# SGWB_circuit.net
KiCad netlist of a schematic drawn in EAGLE
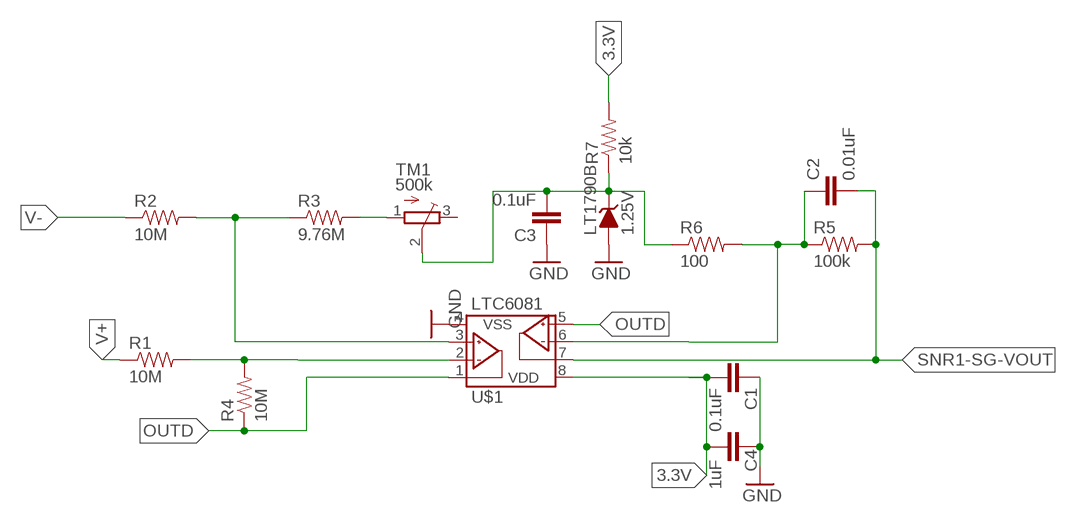
[diagram p0: schematic, sheet 1]

(export (version "E")
  (design (tool "Eeschema 10.0.6"))
  (components
    (comp (ref "C1")
      (value "0.1uF")
      (footprint "eagle-import:0805")
      (libsource (lib "eagle-import") (part "CAP0805"))
    )
    (comp (ref "C2")
      (value "0.01uF")
      (footprint "eagle-import:0805")
      (libsource (lib "eagle-import") (part "CAP0805"))
    )
    (comp (ref "C3")
      (value "0.1uF")
      (footprint "eagle-import:0805")
      (libsource (lib "eagle-import") (part "CAP0805"))
    )
    (comp (ref "C4")
      (value "1uF")
      (footprint "eagle-import:0805")
      (libsource (lib "eagle-import") (part "CAP0805"))
    )
    (comp (ref "LT1790B")
      (value "1.25V")
      (footprint "eagle-import:0805_D")
      (libsource (lib "eagle-import") (part "DIODE_ZENER0805"))
    )
    (comp (ref "R1")
      (value "10M")
      (footprint "eagle-import:0805")
      (libsource (lib "eagle-import") (part "RESISTOR0805-RES"))
    )
    (comp (ref "R2")
      (value "10M")
      (footprint "eagle-import:0805")
      (libsource (lib "eagle-import") (part "RESISTOR0805-RES"))
    )
    (comp (ref "R3")
      (value "9.76M")
      (footprint "eagle-import:0805")
      (libsource (lib "eagle-import") (part "RESISTOR0805-RES"))
    )
    (comp (ref "R4")
      (value "10M")
      (footprint "eagle-import:0805")
      (libsource (lib "eagle-import") (part "RESISTOR0805-RES"))
    )
    (comp (ref "R5")
      (value "100k")
      (footprint "eagle-import:0805")
      (libsource (lib "eagle-import") (part "RESISTOR0805-RES"))
    )
    (comp (ref "R6")
      (value "100")
      (footprint "eagle-import:0805")
      (libsource (lib "eagle-import") (part "RESISTOR0805-RES"))
    )
    (comp (ref "R7")
      (value "10k")
      (footprint "eagle-import:0805")
      (libsource (lib "eagle-import") (part "RESISTOR0805-RES"))
    )
    (comp (ref "TM1")
      (value "500k")
      (footprint "eagle-import:TC33X")
      (libsource (lib "eagle-import") (part "TRIMPOTTC33X"))
    )
    (comp (ref "U$1")
      (value "LTC6081")
      (footprint "eagle-import:MSOP-8_MS")
      (libsource (lib "eagle-import") (part "LTC6081"))
    )
  )
  (nets
    (net (code "1") (name "3.3V") (class "Default")
      (node (ref "C1") (pin "2") (pinfunction "2_2") (pintype "passive"))
      (node (ref "C4") (pin "1") (pinfunction "1_1") (pintype "passive"))
      (node (ref "R7") (pin "2") (pinfunction "2_2") (pintype "passive"))
      (node (ref "U$1") (pin "8") (pinfunction "VDD_8") (pintype "passive"))
    )
    (net (code "2") (name "GND") (class "Default")
      (node (ref "C1") (pin "1") (pinfunction "1_1") (pintype "passive"))
      (node (ref "C3") (pin "1") (pinfunction "1_1") (pintype "passive"))
      (node (ref "C4") (pin "2") (pinfunction "2_2") (pintype "passive"))
      (node (ref "LT1790B") (pin "A") (pinfunction "A_A") (pintype "passive"))
      (node (ref "U$1") (pin "4") (pinfunction "VSS_4") (pintype "passive"))
    )
    (net (code "3") (name "Net-(TM1-A)") (class "Default")
      (node (ref "R3") (pin "2") (pinfunction "2_2") (pintype "passive"))
      (node (ref "TM1") (pin "1") (pinfunction "A_1") (pintype "passive"))
    )
    (net (code "4") (name "Net-(TM1-S)") (class "Default")
      (node (ref "C3") (pin "2") (pinfunction "2_2") (pintype "passive"))
      (node (ref "LT1790B") (pin "C") (pinfunction "C_C") (pintype "passive"))
      (node (ref "R6") (pin "1") (pinfunction "1_1") (pintype "passive"))
      (node (ref "R7") (pin "1") (pinfunction "1_1") (pintype "passive"))
      (node (ref "TM1") (pin "2") (pinfunction "S_2") (pintype "passive"))
    )
    (net (code "5") (name "Net-(U$1-VINA+)") (class "Default")
      (node (ref "R2") (pin "2") (pinfunction "2_2") (pintype "passive"))
      (node (ref "R3") (pin "1") (pinfunction "1_1") (pintype "passive"))
      (node (ref "U$1") (pin "3") (pinfunction "VINA+_3") (pintype "passive"))
    )
    (net (code "6") (name "Net-(U$1-VINA-)") (class "Default")
      (node (ref "R1") (pin "2") (pinfunction "2_2") (pintype "passive"))
      (node (ref "R4") (pin "2") (pinfunction "2_2") (pintype "passive"))
      (node (ref "U$1") (pin "2") (pinfunction "VINA-_2") (pintype "passive"))
    )
    (net (code "7") (name "Net-(U$1-VINB-)") (class "Default")
      (node (ref "C2") (pin "1") (pinfunction "1_1") (pintype "passive"))
      (node (ref "R5") (pin "1") (pinfunction "1_1") (pintype "passive"))
      (node (ref "R6") (pin "2") (pinfunction "2_2") (pintype "passive"))
      (node (ref "U$1") (pin "6") (pinfunction "VINB-_6") (pintype "passive"))
    )
    (net (code "8") (name "OUTD") (class "Default")
      (node (ref "R4") (pin "1") (pinfunction "1_1") (pintype "passive"))
      (node (ref "U$1") (pin "1") (pinfunction "VOUTA_1") (pintype "passive"))
      (node (ref "U$1") (pin "5") (pinfunction "VINB+_5") (pintype "passive"))
    )
    (net (code "9") (name "SNR1-SG-VOUT") (class "Default")
      (node (ref "C2") (pin "2") (pinfunction "2_2") (pintype "passive"))
      (node (ref "R5") (pin "2") (pinfunction "2_2") (pintype "passive"))
      (node (ref "U$1") (pin "7") (pinfunction "VOUTB_7") (pintype "passive"))
    )
    (net (code "10") (name "V+") (class "Default")
      (node (ref "R1") (pin "1") (pinfunction "1_1") (pintype "passive"))
    )
    (net (code "11") (name "V-") (class "Default")
      (node (ref "R2") (pin "1") (pinfunction "1_1") (pintype "passive"))
    )
    (net (code "12") (name "unconnected-(TM1-E-Pad3)") (class "Default")
      (node (ref "TM1") (pin "3") (pinfunction "E_3") (pintype "passive"))
    )
  )
)
